# Schematic_Openbook.net
KiCad netlist of a schematic drawn in EAGLE
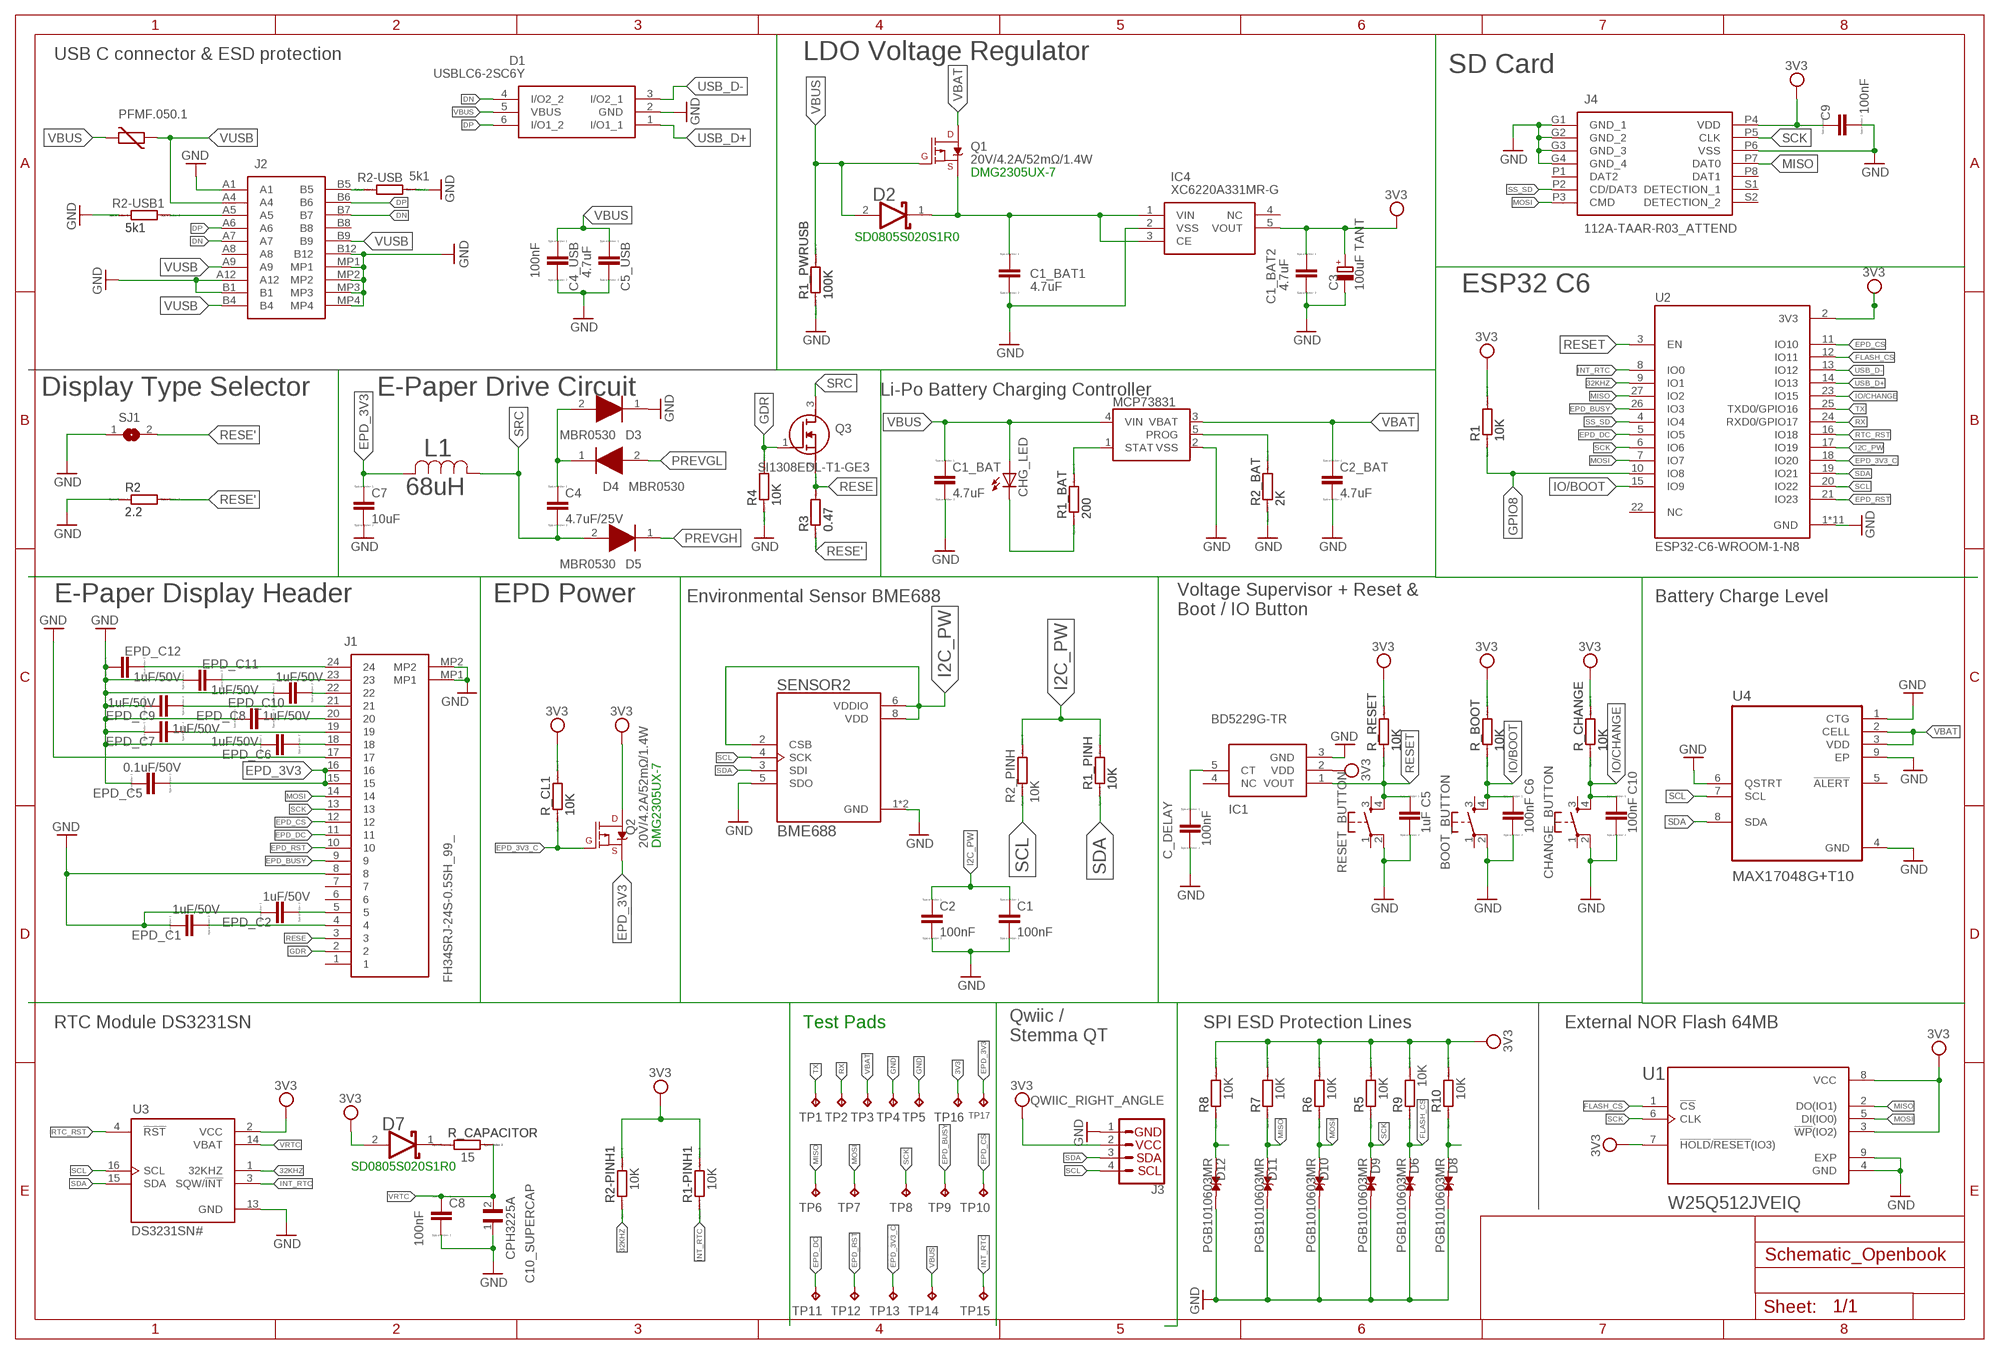
[diagram p0: schematic, sheet 1]

(export (version "E")
  (design (tool "Eeschema 10.0.6"))
  (components
    (comp (ref "BOOT_BUTTON")
      (value "BUTTON_CUSYOMV1")
      (footprint "eagle-import:MYBUTTON")
      (libsource (lib "eagle-import") (part "BUTTON_CUSYOMV1"))
    )
    (comp (ref "C1")
      (value "100nF")
      (footprint "eagle-import:ESP32_WROVER_EAGLE-LTSPICE_C0402")
      (libsource (lib "eagle-import") (part "ESP32_WROVER_EAGLE-LTSPICE_CC0402"))
    )
    (comp (ref "C1_BAT")
      (value "4.7uF")
      (footprint "eagle-import:ESP32_WROVER_EAGLE-LTSPICE_C0402")
      (libsource (lib "eagle-import") (part "ESP32_WROVER_EAGLE-LTSPICE_CC0402"))
    )
    (comp (ref "C1_BAT1")
      (value "4.7uF")
      (footprint "eagle-import:ESP32_WROVER_EAGLE-LTSPICE_C0402")
      (libsource (lib "eagle-import") (part "ESP32_WROVER_EAGLE-LTSPICE_CC0402"))
    )
    (comp (ref "C1_BAT2")
      (value "4.7uF")
      (footprint "eagle-import:ESP32_WROVER_EAGLE-LTSPICE_C0402")
      (libsource (lib "eagle-import") (part "ESP32_WROVER_EAGLE-LTSPICE_CC0402"))
    )
    (comp (ref "C2")
      (value "100nF")
      (footprint "eagle-import:ESP32_WROVER_EAGLE-LTSPICE_C0402")
      (libsource (lib "eagle-import") (part "ESP32_WROVER_EAGLE-LTSPICE_CC0402"))
    )
    (comp (ref "C2_BAT")
      (value "4.7uF")
      (footprint "eagle-import:ESP32_WROVER_EAGLE-LTSPICE_C0402")
      (libsource (lib "eagle-import") (part "ESP32_WROVER_EAGLE-LTSPICE_CC0402"))
    )
    (comp (ref "C3")
      (value "100uF TANT")
      (footprint "eagle-import:RCL_CT3528")
      (libsource (lib "eagle-import") (part "RCL_CPOL-EUCT3528"))
    )
    (comp (ref "C4")
      (value "4.7uF/25V")
      (footprint "eagle-import:ESP32_WROVER_EAGLE-LTSPICE_C0402")
      (libsource (lib "eagle-import") (part "ESP32_WROVER_EAGLE-LTSPICE_CC0402"))
    )
    (comp (ref "C4_USB")
      (value "100nF")
      (footprint "eagle-import:ESP32_WROVER_EAGLE-LTSPICE_C0402")
      (libsource (lib "eagle-import") (part "ESP32_WROVER_EAGLE-LTSPICE_CC0402"))
    )
    (comp (ref "C5")
      (value "1uF")
      (footprint "eagle-import:ESP32_WROVER_EAGLE-LTSPICE_C0402")
      (libsource (lib "eagle-import") (part "ESP32_WROVER_EAGLE-LTSPICE_CC0402"))
    )
    (comp (ref "C5_USB")
      (value "4.7uF")
      (footprint "eagle-import:ESP32_WROVER_EAGLE-LTSPICE_C0402")
      (libsource (lib "eagle-import") (part "ESP32_WROVER_EAGLE-LTSPICE_CC0402"))
    )
    (comp (ref "C6")
      (value "100nF")
      (footprint "eagle-import:ESP32_WROVER_EAGLE-LTSPICE_C0402")
      (libsource (lib "eagle-import") (part "ESP32_WROVER_EAGLE-LTSPICE_CC0402"))
    )
    (comp (ref "C7")
      (value "10uF")
      (footprint "eagle-import:ESP32_WROVER_EAGLE-LTSPICE_C0402")
      (libsource (lib "eagle-import") (part "ESP32_WROVER_EAGLE-LTSPICE_CC0402"))
    )
    (comp (ref "C8")
      (value "100nF")
      (footprint "eagle-import:ESP32_WROVER_EAGLE-LTSPICE_C0402")
      (libsource (lib "eagle-import") (part "ESP32_WROVER_EAGLE-LTSPICE_CC0402"))
    )
    (comp (ref "C9")
      (value "100nF")
      (footprint "eagle-import:ESP32_WROVER_EAGLE-LTSPICE_C0402")
      (libsource (lib "eagle-import") (part "ESP32_WROVER_EAGLE-LTSPICE_CC0402"))
    )
    (comp (ref "C10")
      (value "100nF")
      (footprint "eagle-import:ESP32_WROVER_EAGLE-LTSPICE_C0402")
      (libsource (lib "eagle-import") (part "ESP32_WROVER_EAGLE-LTSPICE_CC0402"))
    )
    (comp (ref "C10_SUPERCAP")
      (value "CPH3225A")
      (footprint "eagle-import:CAPCP3225X100N")
      (fields (field (name "MF") "Seiko Instruments"))
      (libsource (lib "eagle-import") (part "CPH3225A"))
    )
    (comp (ref "CHANGE_BUTTON")
      (value "BUTTON_CUSYOMV1")
      (footprint "eagle-import:MYBUTTON")
      (libsource (lib "eagle-import") (part "BUTTON_CUSYOMV1"))
    )
    (comp (ref "CHG_LED")
      (value "ADAFRUIT_LEDCHIP-LED0603")
      (footprint "eagle-import:ADAFRUIT_CHIP-LED0603")
      (libsource (lib "eagle-import") (part "ADAFRUIT_LEDCHIP-LED0603"))
    )
    (comp (ref "C_DELAY")
      (value "100nF")
      (footprint "eagle-import:ESP32_WROVER_EAGLE-LTSPICE_C0402")
      (libsource (lib "eagle-import") (part "ESP32_WROVER_EAGLE-LTSPICE_CC0402"))
    )
    (comp (ref "D1")
      (value "USBLC6-2SC6Y")
      (footprint "eagle-import:SOT95P280X145-6N")
      (fields (field (name "MF") "STMicroelectronics"))
      (libsource (lib "eagle-import") (part "USBLC6-2SC6Y"))
    )
    (comp (ref "D2")
      (value "SD0805S020S1R0")
      (footprint "eagle-import:ESP32_WROVER_AVX---SD0805S020S1R0_AVX_SD0805S020S1R0_0")
      (fields
        (field (name "DIGIKEY_PART_NUMBER") "478-7800-1-ND")
        (field (name "MF") "AVX")
        (field (name "MOUSER_PART_NUMBER") "581-SD0805S020S1R0")
      )
      (libsource (lib "eagle-import") (part "ESP32_WROVER_AVX---SD0805S020S1R0_AVX_SD0805S020S1R0_0_0AVX_SD0805S020S1R0_0_0"))
    )
    (comp (ref "D3")
      (value "MBR0530")
      (footprint "eagle-import:SOD3716X135N")
      (fields (field (name "MF") "ON Semiconductor"))
      (libsource (lib "eagle-import") (part "MBR0530"))
    )
    (comp (ref "D4")
      (value "MBR0530")
      (footprint "eagle-import:SOD3716X135N")
      (fields (field (name "MF") "ON Semiconductor"))
      (libsource (lib "eagle-import") (part "MBR0530"))
    )
    (comp (ref "D5")
      (value "MBR0530")
      (footprint "eagle-import:SOD3716X135N")
      (fields (field (name "MF") "ON Semiconductor"))
      (libsource (lib "eagle-import") (part "MBR0530"))
    )
    (comp (ref "D6")
      (value "PGB1010603MR")
      (footprint "eagle-import:DIOC1608X36N")
      (fields (field (name "MF") "Littelfuse Inc."))
      (libsource (lib "eagle-import") (part "PGB1010603MR"))
    )
    (comp (ref "D7")
      (value "SD0805S020S1R0")
      (footprint "eagle-import:ESP32_WROVER_AVX---SD0805S020S1R0_AVX_SD0805S020S1R0_0")
      (fields
        (field (name "DIGIKEY_PART_NUMBER") "478-7800-1-ND")
        (field (name "MF") "AVX")
        (field (name "MOUSER_PART_NUMBER") "581-SD0805S020S1R0")
      )
      (libsource (lib "eagle-import") (part "ESP32_WROVER_AVX---SD0805S020S1R0_AVX_SD0805S020S1R0_0_0AVX_SD0805S020S1R0_0_0"))
    )
    (comp (ref "D8")
      (value "PGB1010603MR")
      (footprint "eagle-import:DIOC1608X36N")
      (fields (field (name "MF") "Littelfuse Inc."))
      (libsource (lib "eagle-import") (part "PGB1010603MR"))
    )
    (comp (ref "D9")
      (value "PGB1010603MR")
      (footprint "eagle-import:DIOC1608X36N")
      (fields (field (name "MF") "Littelfuse Inc."))
      (libsource (lib "eagle-import") (part "PGB1010603MR"))
    )
    (comp (ref "D10")
      (value "PGB1010603MR")
      (footprint "eagle-import:DIOC1608X36N")
      (fields (field (name "MF") "Littelfuse Inc."))
      (libsource (lib "eagle-import") (part "PGB1010603MR"))
    )
    (comp (ref "D11")
      (value "PGB1010603MR")
      (footprint "eagle-import:DIOC1608X36N")
      (fields (field (name "MF") "Littelfuse Inc."))
      (libsource (lib "eagle-import") (part "PGB1010603MR"))
    )
    (comp (ref "D12")
      (value "PGB1010603MR")
      (footprint "eagle-import:DIOC1608X36N")
      (fields (field (name "MF") "Littelfuse Inc."))
      (libsource (lib "eagle-import") (part "PGB1010603MR"))
    )
    (comp (ref "EPD_C1")
      (value "1uF/50V")
      (footprint "eagle-import:ESP32_WROVER_EAGLE-LTSPICE_C0402")
      (libsource (lib "eagle-import") (part "ESP32_WROVER_EAGLE-LTSPICE_CC0402"))
    )
    (comp (ref "EPD_C2")
      (value "1uF/50V")
      (footprint "eagle-import:ESP32_WROVER_EAGLE-LTSPICE_C0402")
      (libsource (lib "eagle-import") (part "ESP32_WROVER_EAGLE-LTSPICE_CC0402"))
    )
    (comp (ref "EPD_C5")
      (value "0.1uF/50V")
      (footprint "eagle-import:ESP32_WROVER_EAGLE-LTSPICE_C0402")
      (libsource (lib "eagle-import") (part "ESP32_WROVER_EAGLE-LTSPICE_CC0402"))
    )
    (comp (ref "EPD_C6")
      (value "1uF/50V")
      (footprint "eagle-import:ESP32_WROVER_EAGLE-LTSPICE_C0402")
      (libsource (lib "eagle-import") (part "ESP32_WROVER_EAGLE-LTSPICE_CC0402"))
    )
    (comp (ref "EPD_C7")
      (value "1uF/50V")
      (footprint "eagle-import:ESP32_WROVER_EAGLE-LTSPICE_C0402")
      (libsource (lib "eagle-import") (part "ESP32_WROVER_EAGLE-LTSPICE_CC0402"))
    )
    (comp (ref "EPD_C8")
      (value "1uF/50V")
      (footprint "eagle-import:ESP32_WROVER_EAGLE-LTSPICE_C0402")
      (libsource (lib "eagle-import") (part "ESP32_WROVER_EAGLE-LTSPICE_CC0402"))
    )
    (comp (ref "EPD_C9")
      (value "1uF/50V")
      (footprint "eagle-import:ESP32_WROVER_EAGLE-LTSPICE_C0402")
      (libsource (lib "eagle-import") (part "ESP32_WROVER_EAGLE-LTSPICE_CC0402"))
    )
    (comp (ref "EPD_C10")
      (value "1uF/50V")
      (footprint "eagle-import:ESP32_WROVER_EAGLE-LTSPICE_C0402")
      (libsource (lib "eagle-import") (part "ESP32_WROVER_EAGLE-LTSPICE_CC0402"))
    )
    (comp (ref "EPD_C11")
      (value "1uF/50V")
      (footprint "eagle-import:ESP32_WROVER_EAGLE-LTSPICE_C0402")
      (libsource (lib "eagle-import") (part "ESP32_WROVER_EAGLE-LTSPICE_CC0402"))
    )
    (comp (ref "EPD_C12")
      (value "1uF/50V")
      (footprint "eagle-import:ESP32_WROVER_EAGLE-LTSPICE_C0402")
      (libsource (lib "eagle-import") (part "ESP32_WROVER_EAGLE-LTSPICE_CC0402"))
    )
    (comp (ref "IC1")
      (value "BD5229G-TR")
      (footprint "eagle-import:SOT95P280X125-5N")
      (fields (field (name "MOUSER_PART_NUMBER") "755-BD5229G-TR"))
      (libsource (lib "eagle-import") (part "BD5229G-TR"))
    )
    (comp (ref "IC4")
      (value "XC6220A331MR-G")
      (footprint "eagle-import:SOT95P280X120-5N")
      (fields (field (name "MOUSER_PART_NUMBER") "865-XC6220A331MR-G"))
      (libsource (lib "eagle-import") (part "XC6220A331MR-G"))
    )
    (comp (ref "J1")
      (value "FH34SRJ-24S-0.5SH_99_")
      (footprint "eagle-import:FH34SRJ24S05SH99")
      (fields
        (field (name "MANUFACTURER_PART_NUMBER") "FH34SRJ-24S-0.5SH(99)")
        (field (name "MOUSER_PART_NUMBER") "798-FH34SRJ24S05SH99")
      )
      (libsource (lib "eagle-import") (part "FH34SRJ-24S-0.5SH_99_"))
    )
    (comp (ref "J2")
      (value "SAMACSYS_PARTS_USB4110-GF-A")
      (footprint "eagle-import:SAMACSYS_PARTS_USB4110GFA")
      (fields
        (field (name "MANUFACTURER_PART_NUMBER") "USB4110-GF-A")
        (field (name "MOUSER_PART_NUMBER") "640-USB4110-GF-A")
      )
      (libsource (lib "eagle-import") (part "SAMACSYS_PARTS_USB4110-GF-A"))
    )
    (comp (ref "J3")
      (value "QWIIC_RIGHT_ANGLE")
      (footprint "eagle-import:JST04_1MM_RA")
      (libsource (lib "eagle-import") (part "QWIIC_CONNECTORJS-1MM"))
    )
    (comp (ref "J4")
      (value "112A-TAAR-R03_ATTEND")
      (footprint "eagle-import:112ATAARR03ATTEND")
      (fields (field (name "MANUFACTURER_PART_NUMBER") "112A-TAAR-R03 ATTEND"))
      (libsource (lib "eagle-import") (part "112A-TAAR-R03_ATTEND"))
    )
    (comp (ref "L1")
      (value "68uH")
      (footprint "eagle-import:IND_4828-WE-TPC_WRE")
      (fields
        (field (name "MANUFACTURER_PART_NUMBER") "744043680")
        (field (name "COPYRIGHT") "Copyright (C) 2024 Ultra Librarian. All rights reserved.")
      )
      (libsource (lib "eagle-import") (part "744043680IND_4828-WE-TPC_WRE"))
    )
    (comp (ref "MCP73831")
      (value "ESP32_WROVER_SPARKFUN-IC-POWER_MCP73831")
      (footprint "eagle-import:ESP32_WROVER_SPARKFUN-IC-POWER_SOT23-5")
      (libsource (lib "eagle-import") (part "ESP32_WROVER_SPARKFUN-IC-POWER_MCP73831"))
    )
    (comp (ref "PFMF.050.1")
      (value "ESP32C6_VARISTORCN1812")
      (footprint "eagle-import:ESP32C6_VARISTOR_CT_CN1812")
      (libsource (lib "eagle-import") (part "ESP32C6_VARISTORCN1812"))
    )
    (comp (ref "Q1")
      (value "20V/4.2A/52mΩ/1.4W")
      (footprint "eagle-import:ESP32_WROVER_SPARKFUN-DISCRETESEMI_SOT23-3")
      (libsource (lib "eagle-import") (part "ESP32_WROVER_SPARKFUN-DISCRETESEMI_MOSFET_PCH-DMG2305UX-7"))
    )
    (comp (ref "Q2")
      (value "20V/4.2A/52mΩ/1.4W")
      (footprint "eagle-import:ESP32_WROVER_SPARKFUN-DISCRETESEMI_SOT23-3")
      (libsource (lib "eagle-import") (part "ESP32_WROVER_SPARKFUN-DISCRETESEMI_MOSFET_PCH-DMG2305UX-7"))
    )
    (comp (ref "Q3")
      (value "SI1308EDL-T1-GE3")
      (footprint "eagle-import:SOT65P210X110-3N")
      (fields (field (name "MF") "Vishay Siliconix"))
      (libsource (lib "eagle-import") (part "SI1308EDL-T1-GE3"))
    )
    (comp (ref "R1")
      (value "10K")
      (footprint "eagle-import:ESP32_WROVER_EAGLE-LTSPICE_R0402")
      (libsource (lib "eagle-import") (part "ESP32_WROVER_EAGLE-LTSPICE_RR0402"))
    )
    (comp (ref "R1-PINH1")
      (value "10K")
      (footprint "eagle-import:ESP32_WROVER_EAGLE-LTSPICE_R0402")
      (libsource (lib "eagle-import") (part "ESP32_WROVER_EAGLE-LTSPICE_RR0402"))
    )
    (comp (ref "R1_BAT")
      (value "200")
      (footprint "eagle-import:ESP32_WROVER_EAGLE-LTSPICE_R0402")
      (libsource (lib "eagle-import") (part "ESP32_WROVER_EAGLE-LTSPICE_RR0402"))
    )
    (comp (ref "R1_PINH")
      (value "10K")
      (footprint "eagle-import:ESP32_WROVER_EAGLE-LTSPICE_R0402")
      (libsource (lib "eagle-import") (part "ESP32_WROVER_EAGLE-LTSPICE_RR0402"))
    )
    (comp (ref "R1_PWRUSB")
      (value "100K")
      (footprint "eagle-import:ESP32_WROVER_EAGLE-LTSPICE_R0402")
      (libsource (lib "eagle-import") (part "ESP32_WROVER_EAGLE-LTSPICE_RR0402"))
    )
    (comp (ref "R2")
      (value "2.2")
      (footprint "eagle-import:ESP32_WROVER_EAGLE-LTSPICE_R0402")
      (libsource (lib "eagle-import") (part "ESP32_WROVER_EAGLE-LTSPICE_RR0402"))
    )
    (comp (ref "R2-PINH1")
      (value "10K")
      (footprint "eagle-import:ESP32_WROVER_EAGLE-LTSPICE_R0402")
      (libsource (lib "eagle-import") (part "ESP32_WROVER_EAGLE-LTSPICE_RR0402"))
    )
    (comp (ref "R2-USB")
      (value "5k1")
      (footprint "eagle-import:ESP32_WROVER_EAGLE-LTSPICE_R0402")
      (libsource (lib "eagle-import") (part "ESP32_WROVER_EAGLE-LTSPICE_RR0402"))
    )
    (comp (ref "R2-USB1")
      (value "5k1")
      (footprint "eagle-import:ESP32_WROVER_EAGLE-LTSPICE_R0402")
      (libsource (lib "eagle-import") (part "ESP32_WROVER_EAGLE-LTSPICE_RR0402"))
    )
    (comp (ref "R2_BAT")
      (value "2K")
      (footprint "eagle-import:ESP32_WROVER_EAGLE-LTSPICE_R0402")
      (libsource (lib "eagle-import") (part "ESP32_WROVER_EAGLE-LTSPICE_RR0402"))
    )
    (comp (ref "R2_PINH")
      (value "10K")
      (footprint "eagle-import:ESP32_WROVER_EAGLE-LTSPICE_R0402")
      (libsource (lib "eagle-import") (part "ESP32_WROVER_EAGLE-LTSPICE_RR0402"))
    )
    (comp (ref "R3")
      (value "0.47")
      (footprint "eagle-import:ESP32_WROVER_EAGLE-LTSPICE_R0402")
      (libsource (lib "eagle-import") (part "ESP32_WROVER_EAGLE-LTSPICE_RR0402"))
    )
    (comp (ref "R4")
      (value "10K")
      (footprint "eagle-import:ESP32_WROVER_EAGLE-LTSPICE_R0402")
      (libsource (lib "eagle-import") (part "ESP32_WROVER_EAGLE-LTSPICE_RR0402"))
    )
    (comp (ref "R5")
      (value "10K")
      (footprint "eagle-import:ESP32_WROVER_EAGLE-LTSPICE_R0402")
      (libsource (lib "eagle-import") (part "ESP32_WROVER_EAGLE-LTSPICE_RR0402"))
    )
    (comp (ref "R6")
      (value "10K")
      (footprint "eagle-import:ESP32_WROVER_EAGLE-LTSPICE_R0402")
      (libsource (lib "eagle-import") (part "ESP32_WROVER_EAGLE-LTSPICE_RR0402"))
    )
    (comp (ref "R7")
      (value "10K")
      (footprint "eagle-import:ESP32_WROVER_EAGLE-LTSPICE_R0402")
      (libsource (lib "eagle-import") (part "ESP32_WROVER_EAGLE-LTSPICE_RR0402"))
    )
    (comp (ref "R8")
      (value "10K")
      (footprint "eagle-import:ESP32_WROVER_EAGLE-LTSPICE_R0402")
      (libsource (lib "eagle-import") (part "ESP32_WROVER_EAGLE-LTSPICE_RR0402"))
    )
    (comp (ref "R9")
      (value "10K")
      (footprint "eagle-import:ESP32_WROVER_EAGLE-LTSPICE_R0402")
      (libsource (lib "eagle-import") (part "ESP32_WROVER_EAGLE-LTSPICE_RR0402"))
    )
    (comp (ref "R10")
      (value "10K")
      (footprint "eagle-import:ESP32_WROVER_EAGLE-LTSPICE_R0402")
      (libsource (lib "eagle-import") (part "ESP32_WROVER_EAGLE-LTSPICE_RR0402"))
    )
    (comp (ref "RESET_BUTTON")
      (value "BUTTON_CUSYOMV1")
      (footprint "eagle-import:MYBUTTON")
      (libsource (lib "eagle-import") (part "BUTTON_CUSYOMV1"))
    )
    (comp (ref "R_BOOT")
      (value "10K")
      (footprint "eagle-import:ESP32_WROVER_EAGLE-LTSPICE_R0402")
      (libsource (lib "eagle-import") (part "ESP32_WROVER_EAGLE-LTSPICE_RR0402"))
    )
    (comp (ref "R_CAPACITOR")
      (value "15")
      (footprint "eagle-import:ESP32_WROVER_EAGLE-LTSPICE_R0402")
      (libsource (lib "eagle-import") (part "ESP32_WROVER_EAGLE-LTSPICE_RR0402"))
    )
    (comp (ref "R_CHANGE")
      (value "10K")
      (footprint "eagle-import:ESP32_WROVER_EAGLE-LTSPICE_R0402")
      (libsource (lib "eagle-import") (part "ESP32_WROVER_EAGLE-LTSPICE_RR0402"))
    )
    (comp (ref "R_CL1")
      (value "10K")
      (footprint "eagle-import:ESP32_WROVER_EAGLE-LTSPICE_R0402")
      (libsource (lib "eagle-import") (part "ESP32_WROVER_EAGLE-LTSPICE_RR0402"))
    )
    (comp (ref "R_RESET")
      (value "10K")
      (footprint "eagle-import:ESP32_WROVER_EAGLE-LTSPICE_R0402")
      (libsource (lib "eagle-import") (part "ESP32_WROVER_EAGLE-LTSPICE_RR0402"))
    )
    (comp (ref "SENSOR2")
      (value "BME688")
      (footprint "eagle-import:ESP32_WROVER_BME680_PSON80P300X300X100-8N")
      (fields (field (name "MF") "Bosch Sensortec") (field (name "MP") "BME680"))
      (libsource (lib "eagle-import") (part "ESP32_WROVER_BME680_BME680"))
    )
    (comp (ref "SJ1") (value "SJ") (footprint "eagle-import:SJ") (libsource (lib "eagle-import") (part "SJ")))
    (comp (ref "TP1")
      (value "TPTP20R")
      (footprint "eagle-import:TP20R")
      (libsource (lib "eagle-import") (part "TPTP20R"))
    )
    (comp (ref "TP2")
      (value "TPTP20R")
      (footprint "eagle-import:TP20R")
      (libsource (lib "eagle-import") (part "TPTP20R"))
    )
    (comp (ref "TP3")
      (value "TPTP20R")
      (footprint "eagle-import:TP20R")
      (libsource (lib "eagle-import") (part "TPTP20R"))
    )
    (comp (ref "TP4")
      (value "TPTP20R")
      (footprint "eagle-import:TP20R")
      (libsource (lib "eagle-import") (part "TPTP20R"))
    )
    (comp (ref "TP5")
      (value "TPTP20R")
      (footprint "eagle-import:TP20R")
      (libsource (lib "eagle-import") (part "TPTP20R"))
    )
    (comp (ref "TP6")
      (value "TPTP20R")
      (footprint "eagle-import:TP20R")
      (libsource (lib "eagle-import") (part "TPTP20R"))
    )
    (comp (ref "TP7")
      (value "TPTP20R")
      (footprint "eagle-import:TP20R")
      (libsource (lib "eagle-import") (part "TPTP20R"))
    )
    (comp (ref "TP8")
      (value "TPTP20R")
      (footprint "eagle-import:TP20R")
      (libsource (lib "eagle-import") (part "TPTP20R"))
    )
    (comp (ref "TP9")
      (value "TPTP20R")
      (footprint "eagle-import:TP20R")
      (libsource (lib "eagle-import") (part "TPTP20R"))
    )
    (comp (ref "TP10")
      (value "TPTP20R")
      (footprint "eagle-import:TP20R")
      (libsource (lib "eagle-import") (part "TPTP20R"))
    )
    (comp (ref "TP11")
      (value "TPTP20R")
      (footprint "eagle-import:TP20R")
      (libsource (lib "eagle-import") (part "TPTP20R"))
    )
    (comp (ref "TP12")
      (value "TPTP20R")
      (footprint "eagle-import:TP20R")
      (libsource (lib "eagle-import") (part "TPTP20R"))
    )
    (comp (ref "TP13")
      (value "TPTP20R")
      (footprint "eagle-import:TP20R")
      (libsource (lib "eagle-import") (part "TPTP20R"))
    )
    (comp (ref "TP14")
      (value "TPTP20R")
      (footprint "eagle-import:TP20R")
      (libsource (lib "eagle-import") (part "TPTP20R"))
    )
    (comp (ref "TP15")
      (value "TPTP20R")
      (footprint "eagle-import:TP20R")
      (libsource (lib "eagle-import") (part "TPTP20R"))
    )
    (comp (ref "TP16")
      (value "TPTP20R")
      (footprint "eagle-import:TP20R")
      (libsource (lib "eagle-import") (part "TPTP20R"))
    )
    (comp (ref "TP17")
      (value "TPTP20R")
      (footprint "eagle-import:TP20R")
      (libsource (lib "eagle-import") (part "TPTP20R"))
    )
    (comp (ref "U1")
      (value "W25Q512JVEIQ")
      (footprint "eagle-import:SON127P600X800X80-9N")
      (fields (field (name "MF") "Winbond Electronics"))
      (libsource (lib "eagle-import") (part "W25Q512JVEIQ"))
    )
    (comp (ref "U2")
      (value "ESP32-C6-WROOM-1-N8")
      (footprint "eagle-import:XCVR_ESP32-C6-WROOM-1-N8")
      (fields (field (name "MF") "Espressif Systems"))
      (libsource (lib "eagle-import") (part "ESP32-C6-WROOM-1-N8"))
    )
    (comp (ref "U3")
      (value "DS3231SN#")
      (footprint "eagle-import:SOIC127P1032X265-16N")
      (fields (field (name "MF") "Analog Devices"))
      (libsource (lib "eagle-import") (part "DS3231SN#"))
    )
    (comp (ref "U4")
      (value "MAX17048G+T10")
      (footprint "eagle-import:SON50P200X200X80-9N")
      (fields (field (name "MF") "Analog Devices"))
      (libsource (lib "eagle-import") (part "MAX17048G+T10"))
    )
  )
  (nets
    (net (code "1") (name "3V3") (class "Default")
      (node (ref "C1_BAT2") (pin "1") (pinfunction "1_1") (pintype "passive"))
      (node (ref "C3") (pin "+") (pinfunction "+_+") (pintype "passive"))
      (node (ref "C9") (pin "1") (pinfunction "1_1") (pintype "passive"))
      (node (ref "D7") (pin "2") (pinfunction "ANODE_2") (pintype "bidirectional"))
      (node (ref "IC1") (pin "2") (pinfunction "VDD_2") (pintype "bidirectional"))
      (node (ref "IC4") (pin "5") (pinfunction "VOUT_5") (pintype "bidirectional"))
      (node (ref "J3") (pin "2") (pinfunction "2_2") (pintype "power_in"))
      (node (ref "J4") (pin "P4") (pinfunction "VDD_P4") (pintype "bidirectional"))
      (node (ref "Q2") (pin "3") (pinfunction "D_3") (pintype "bidirectional"))
      (node (ref "R1") (pin "2") (pinfunction "2_2") (pintype "passive"))
      (node (ref "R1-PINH1") (pin "2") (pinfunction "2_2") (pintype "passive"))
      (node (ref "R10") (pin "2") (pinfunction "2_2") (pintype "passive"))
      (node (ref "R2-PINH1") (pin "2") (pinfunction "2_2") (pintype "passive"))
      (node (ref "R5") (pin "2") (pinfunction "2_2") (pintype "passive"))
      (node (ref "R6") (pin "2") (pinfunction "2_2") (pintype "passive"))
      (node (ref "R7") (pin "2") (pinfunction "2_2") (pintype "passive"))
      (node (ref "R8") (pin "2") (pinfunction "2_2") (pintype "passive"))
      (node (ref "R9") (pin "2") (pinfunction "2_2") (pintype "passive"))
      (node (ref "R_BOOT") (pin "2") (pinfunction "2_2") (pintype "passive"))
      (node (ref "R_CHANGE") (pin "2") (pinfunction "2_2") (pintype "passive"))
      (node (ref "R_CL1") (pin "2") (pinfunction "2_2") (pintype "passive"))
      (node (ref "R_RESET") (pin "2") (pinfunction "2_2") (pintype "passive"))
      (node (ref "TP16") (pin "TP") (pinfunction "TP_TP") (pintype "input"))
      (node (ref "U1") (pin "3") (pinfunction "~{WP}(IO2)_3") (pintype "bidirectional"))
      (node (ref "U1") (pin "7") (pinfunction "~{HOLD}/~{RESET}(IO3)_7") (pintype "bidirectional"))
      (node (ref "U1") (pin "8") (pinfunction "VCC_8") (pintype "power_in"))
      (node (ref "U2") (pin "2") (pinfunction "3V3_2") (pintype "power_in"))
      (node (ref "U3") (pin "2") (pinfunction "VCC_2") (pintype "power_in"))
    )
    (net (code "2") (name "32KHZ") (class "Default")
      (node (ref "R2-PINH1") (pin "1") (pinfunction "1_1") (pintype "passive"))
      (node (ref "U2") (pin "9") (pinfunction "IO1_9") (pintype "bidirectional"))
      (node (ref "U3") (pin "1") (pinfunction "32KHZ_1") (pintype "output"))
    )
    (net (code "3") (name "DN") (class "Default")
      (node (ref "D1") (pin "4") (pinfunction "I/O2_2_4") (pintype "bidirectional"))
      (node (ref "J2") (pin "A7") (pinfunction "A7_A7") (pintype "bidirectional"))
      (node (ref "J2") (pin "B7") (pinfunction "B7_B7") (pintype "bidirectional"))
    )
    (net (code "4") (name "DP") (class "Default")
      (node (ref "D1") (pin "6") (pinfunction "I/O1_2_6") (pintype "bidirectional"))
      (node (ref "J2") (pin "A6") (pinfunction "A6_A6") (pintype "bidirectional"))
      (node (ref "J2") (pin "B6") (pinfunction "B6_B6") (pintype "bidirectional"))
    )
    (net (code "5") (name "EPD_3V3") (class "Default")
      (node (ref "C7") (pin "1") (pinfunction "1_1") (pintype "passive"))
      (node (ref "EPD_C5") (pin "2") (pinfunction "2_2") (pintype "passive"))
      (node (ref "J1") (pin "15") (pinfunction "15_15") (pintype "bidirectional"))
      (node (ref "J1") (pin "16") (pinfunction "16_16") (pintype "bidirectional"))
      (node (ref "L1") (pin "2") (pinfunction "2_2") (pintype "passive"))
      (node (ref "Q2") (pin "2") (pinfunction "S_2") (pintype "bidirectional"))
      (node (ref "TP17") (pin "TP") (pinfunction "TP_TP") (pintype "input"))
    )
    (net (code "6") (name "EPD_3V3_C") (class "Default")
      (node (ref "Q2") (pin "1") (pinfunction "G_1") (pintype "bidirectional"))
      (node (ref "R_CL1") (pin "1") (pinfunction "1_1") (pintype "passive"))
      (node (ref "TP13") (pin "TP") (pinfunction "TP_TP") (pintype "input"))
      (node (ref "U2") (pin "18") (pinfunction "IO20_18") (pintype "bidirectional"))
    )
    (net (code "7") (name "EPD_BUSY") (class "Default")
      (node (ref "J1") (pin "9") (pinfunction "9_9") (pintype "bidirectional"))
      (node (ref "TP9") (pin "TP") (pinfunction "TP_TP") (pintype "input"))
      (node (ref "U2") (pin "26") (pinfunction "IO3_26") (pintype "bidirectional"))
    )
    (net (code "8") (name "EPD_CS") (class "Default")
      (node (ref "J1") (pin "12") (pinfunction "12_12") (pintype "bidirectional"))
      (node (ref "TP10") (pin "TP") (pinfunction "TP_TP") (pintype "input"))
      (node (ref "U2") (pin "11") (pinfunction "IO10_11") (pintype "bidirectional"))
    )
    (net (code "9") (name "EPD_DC") (class "Default")
      (node (ref "J1") (pin "11") (pinfunction "11_11") (pintype "bidirectional"))
      (node (ref "TP11") (pin "TP") (pinfunction "TP_TP") (pintype "input"))
      (node (ref "U2") (pin "5") (pinfunction "IO5_5") (pintype "bidirectional"))
    )
    (net (code "10") (name "EPD_RST") (class "Default")
      (node (ref "J1") (pin "10") (pinfunction "10_10") (pintype "bidirectional"))
      (node (ref "TP12") (pin "TP") (pinfunction "TP_TP") (pintype "input"))
      (node (ref "U2") (pin "21") (pinfunction "IO23_21") (pintype "bidirectional"))
    )
    (net (code "11") (name "FLASH_CS") (class "Default")
      (node (ref "D6") (pin "1") (pinfunction "1_1") (pintype "passive"))
      (node (ref "R9") (pin "1") (pinfunction "1_1") (pintype "passive"))
      (node (ref "U1") (pin "1") (pinfunction "~{CS}_1") (pintype "input"))
      (node (ref "U2") (pin "12") (pinfunction "IO11_12") (pintype "bidirectional"))
    )
    (net (code "12") (name "GDR") (class "Default")
      (node (ref "J1") (pin "2") (pinfunction "2_2") (pintype "bidirectional"))
      (node (ref "Q3") (pin "1") (pinfunction "G_1") (pintype "bidirectional"))
      (node (ref "R4") (pin "2") (pinfunction "2_2") (pintype "passive"))
    )
    (net (code "13") (name "GND") (class "Default")
      (node (ref "BOOT_BUTTON") (pin "2") (pinfunction "2_2") (pintype "passive"))
      (node (ref "C1") (pin "2") (pinfunction "2_2") (pintype "passive"))
      (node (ref "C10") (pin "2") (pinfunction "2_2") (pintype "passive"))
      (node (ref "C10_SUPERCAP") (pin "1") (pinfunction "1_1") (pintype "passive"))
      (node (ref "C1_BAT") (pin "2") (pinfunction "2_2") (pintype "passive"))
      (node (ref "C1_BAT1") (pin "2") (pinfunction "2_2") (pintype "passive"))
      (node (ref "C1_BAT2") (pin "2") (pinfunction "2_2") (pintype "passive"))
      (node (ref "C2") (pin "2") (pinfunction "2_2") (pintype "passive"))
      (node (ref "C2_BAT") (pin "2") (pinfunction "2_2") (pintype "passive"))
      (node (ref "C3") (pin "-") (pinfunction "-_-") (pintype "passive"))
      (node (ref "C4_USB") (pin "2") (pinfunction "2_2") (pintype "passive"))
      (node (ref "C5") (pin "2") (pinfunction "2_2") (pintype "passive"))
      (node (ref "C5_USB") (pin "2") (pinfunction "2_2") (pintype "passive"))
      (node (ref "C6") (pin "2") (pinfunction "2_2") (pintype "passive"))
      (node (ref "C7") (pin "2") (pinfunction "2_2") (pintype "passive"))
      (node (ref "C8") (pin "2") (pinfunction "2_2") (pintype "passive"))
      (node (ref "C9") (pin "2") (pinfunction "2_2") (pintype "passive"))
      (node (ref "CHANGE_BUTTON") (pin "2") (pinfunction "2_2") (pintype "passive"))
      (node (ref "C_DELAY") (pin "2") (pinfunction "2_2") (pintype "passive"))
      (node (ref "D1") (pin "2") (pinfunction "GND_2") (pintype "bidirectional"))
      (node (ref "D10") (pin "2") (pinfunction "2_2") (pintype "passive"))
      (node (ref "D11") (pin "2") (pinfunction "2_2") (pintype "passive"))
      (node (ref "D12") (pin "2") (pinfunction "2_2") (pintype "passive"))
      (node (ref "D3") (pin "1") (pinfunction "K_1") (pintype "bidirectional"))
      (node (ref "D6") (pin "2") (pinfunction "2_2") (pintype "passive"))
      (node (ref "D8") (pin "2") (pinfunction "2_2") (pintype "passive"))
      (node (ref "D9") (pin "2") (pinfunction "2_2") (pintype "passive"))
      (node (ref "EPD_C1") (pin "1") (pinfunction "1_1") (pintype "passive"))
      (node (ref "EPD_C10") (pin "1") (pinfunction "1_1") (pintype "passive"))
      (node (ref "EPD_C11") (pin "1") (pinfunction "1_1") (pintype "passive"))
      (node (ref "EPD_C12") (pin "1") (pinfunction "1_1") (pintype "passive"))
      (node (ref "EPD_C2") (pin "1") (pinfunction "1_1") (pintype "passive"))
      (node (ref "EPD_C5") (pin "1") (pinfunction "1_1") (pintype "passive"))
      (node (ref "EPD_C6") (pin "1") (pinfunction "1_1") (pintype "passive"))
      (node (ref "EPD_C7") (pin "1") (pinfunction "1_1") (pintype "passive"))
      (node (ref "EPD_C8") (pin "1") (pinfunction "1_1") (pintype "passive"))
      (node (ref "EPD_C9") (pin "1") (pinfunction "1_1") (pintype "passive"))
      (node (ref "IC1") (pin "3") (pinfunction "GND_3") (pintype "bidirectional"))
      (node (ref "IC4") (pin "2") (pinfunction "VSS_2") (pintype "bidirectional"))
      (node (ref "J1") (pin "17") (pinfunction "17_17") (pintype "bidirectional"))
      (node (ref "J1") (pin "8") (pinfunction "8_8") (pintype "bidirectional"))
      (node (ref "J1") (pin "MP1") (pinfunction "MP1_MP1") (pintype "bidirectional"))
      (node (ref "J1") (pin "MP2") (pinfunction "MP2_MP2") (pintype "bidirectional"))
      (node (ref "J2") (pin "A1") (pinfunction "A1_A1") (pintype "bidirectional"))
      (node (ref "J2") (pin "A12") (pinfunction "A12_A12") (pintype "bidirectional"))
      (node (ref "J2") (pin "B1") (pinfunction "B1_B1") (pintype "bidirectional"))
      (node (ref "J2") (pin "B12") (pinfunction "B12_B12") (pintype "bidirectional"))
      (node (ref "J2") (pin "MP1") (pinfunction "MP1_MP1") (pintype "bidirectional"))
      (node (ref "J2") (pin "MP2") (pinfunction "MP2_MP2") (pintype "bidirectional"))
      (node (ref "J2") (pin "MP3") (pinfunction "MP3_MP3") (pintype "bidirectional"))
      (node (ref "J2") (pin "MP4") (pinfunction "MP4_MP4") (pintype "bidirectional"))
      (node (ref "J3") (pin "1") (pinfunction "1_1") (pintype "power_in"))
      (node (ref "J4") (pin "G1") (pinfunction "GND_1_G1") (pintype "bidirectional"))
      (node (ref "J4") (pin "G2") (pinfunction "GND_2_G2") (pintype "bidirectional"))
      (node (ref "J4") (pin "G3") (pinfunction "GND_3_G3") (pintype "bidirectional"))
      (node (ref "J4") (pin "G4") (pinfunction "GND_4_G4") (pintype "bidirectional"))
      (node (ref "J4") (pin "P6") (pinfunction "VSS_P6") (pintype "bidirectional"))
      (node (ref "MCP73831") (pin "2") (pinfunction "VSS_2") (pintype "power_in"))
      (node (ref "R1_PWRUSB") (pin "1") (pinfunction "1_1") (pintype "passive"))
      (node (ref "R2") (pin "1") (pinfunction "1_1") (pintype "passive"))
      (node (ref "R2-USB") (pin "2") (pinfunction "2_2") (pintype "passive"))
      (node (ref "R2-USB1") (pin "1") (pinfunction "1_1") (pintype "passive"))
      (node (ref "R2_BAT") (pin "1") (pinfunction "1_1") (pintype "passive"))
      (node (ref "R4") (pin "1") (pinfunction "1_1") (pintype "passive"))
      (node (ref "RESET_BUTTON") (pin "2") (pinfunction "2_2") (pintype "passive"))
      (node (ref "SENSOR2") (pin "1") (pinfunction "GND_1") (pintype "power_in"))
      (node (ref "SENSOR2") (pin "5") (pinfunction "SDO_5") (pintype "bidirectional"))
      (node (ref "SENSOR2") (pin "7") (pinfunction "GND_7") (pintype "power_in"))
      (node (ref "SJ1") (pin "1") (pinfunction "1_1") (pintype "passive"))
      (node (ref "TP4") (pin "TP") (pinfunction "TP_TP") (pintype "input"))
      (node (ref "TP5") (pin "TP") (pinfunction "TP_TP") (pintype "input"))
      (node (ref "U1") (pin "4") (pinfunction "GND_4") (pintype "power_in"))
      (node (ref "U1") (pin "9") (pinfunction "EXP_9") (pintype "passive"))
      (node (ref "U2") (pin "1") (pinfunction "GND_1") (pintype "power_in"))
      (node (ref "U2") (pin "28") (pinfunction "GND_28") (pintype "power_in"))
      (node (ref "U2") (pin "29_1") (pinfunction "GND_29_1") (pintype "power_in"))
      (node (ref "U2") (pin "29_2") (pinfunction "GND_29_2") (pintype "power_in"))
      (node (ref "U2") (pin "29_3") (pinfunction "GND_29_3") (pintype "power_in"))
      (node (ref "U2") (pin "29_4") (pinfunction "GND_29_4") (pintype "power_in"))
      (node (ref "U2") (pin "29_5") (pinfunction "GND_29_5") (pintype "power_in"))
      (node (ref "U2") (pin "29_6") (pinfunction "GND_29_6") (pintype "power_in"))
      (node (ref "U2") (pin "29_7") (pinfunction "GND_29_7") (pintype "power_in"))
      (node (ref "U2") (pin "29_8") (pinfunction "GND_29_8") (pintype "power_in"))
      (node (ref "U2") (pin "29_9") (pinfunction "GND_29_9") (pintype "power_in"))
      (node (ref "U3") (pin "13") (pinfunction "GND_13") (pintype "power_in"))
      (node (ref "U4") (pin "1") (pinfunction "CTG_1") (pintype "power_in"))
      (node (ref "U4") (pin "4") (pinfunction "GND_4") (pintype "power_in"))
      (node (ref "U4") (pin "6") (pinfunction "QSTRT_6") (pintype "input"))
      (node (ref "U4") (pin "9") (pinfunction "EP_9") (pintype "power_in"))
    )
    (net (code "14") (name "GPIO8") (class "Default")
      (node (ref "R1") (pin "1") (pinfunction "1_1") (pintype "passive"))
      (node (ref "U2") (pin "10") (pinfunction "IO8_10") (pintype "bidirectional"))
    )
    (net (code "15") (name "I2C_PW") (class "Default")
      (node (ref "C1") (pin "1") (pinfunction "1_1") (pintype "passive"))
      (node (ref "C2") (pin "1") (pinfunction "1_1") (pintype "passive"))
      (node (ref "R1_PINH") (pin "2") (pinfunction "2_2") (pintype "passive"))
      (node (ref "R2_PINH") (pin "2") (pinfunction "2_2") (pintype "passive"))
      (node (ref "SENSOR2") (pin "2") (pinfunction "CSB_2") (pintype "input"))
      (node (ref "SENSOR2") (pin "6") (pinfunction "VDDIO_6") (pintype "power_in"))
      (node (ref "SENSOR2") (pin "8") (pinfunction "VDD_8") (pintype "power_in"))
      (node (ref "U2") (pin "17") (pinfunction "IO19_17") (pintype "bidirectional"))
    )
    (net (code "16") (name "INT_RTC") (class "Default")
      (node (ref "R1-PINH1") (pin "1") (pinfunction "1_1") (pintype "passive"))
      (node (ref "TP15") (pin "TP") (pinfunction "TP_TP") (pintype "input"))
      (node (ref "U2") (pin "8") (pinfunction "IO0_8") (pintype "bidirectional"))
      (node (ref "U3") (pin "3") (pinfunction "SQW/~{INT}_3") (pintype "output"))
    )
    (net (code "17") (name "IO{slash}BOOT") (class "Default")
      (node (ref "BOOT_BUTTON") (pin "4") (pinfunction "4_4") (pintype "passive"))
      (node (ref "C6") (pin "1") (pinfunction "1_1") (pintype "passive"))
      (node (ref "R_BOOT") (pin "1") (pinfunction "1_1") (pintype "passive"))
      (node (ref "U2") (pin "15") (pinfunction "IO9_15") (pintype "bidirectional"))
    )
    (net (code "18") (name "IO{slash}CHANGE") (class "Default")
      (node (ref "C10") (pin "1") (pinfunction "1_1") (pintype "passive"))
      (node (ref "CHANGE_BUTTON") (pin "4") (pinfunction "4_4") (pintype "passive"))
      (node (ref "R_CHANGE") (pin "1") (pinfunction "1_1") (pintype "passive"))
      (node (ref "U2") (pin "23") (pinfunction "IO15_23") (pintype "bidirectional"))
    )
    (net (code "19") (name "MISO") (class "Default")
      (node (ref "D11") (pin "1") (pinfunction "1_1") (pintype "passive"))
      (node (ref "J4") (pin "P7") (pinfunction "DAT0_P7") (pintype "bidirectional"))
      (node (ref "R7") (pin "1") (pinfunction "1_1") (pintype "passive"))
      (node (ref "TP6") (pin "TP") (pinfunction "TP_TP") (pintype "input"))
      (node (ref "U1") (pin "2") (pinfunction "DO(IO1)_2") (pintype "bidirectional"))
      (node (ref "U2") (pin "27") (pinfunction "IO2_27") (pintype "bidirectional"))
    )
    (net (code "20") (name "MOSI") (class "Default")
      (node (ref "D10") (pin "1") (pinfunction "1_1") (pintype "passive"))
      (node (ref "J1") (pin "14") (pinfunction "14_14") (pintype "bidirectional"))
      (node (ref "J4") (pin "P3") (pinfunction "CMD_P3") (pintype "bidirectional"))
      (node (ref "R6") (pin "1") (pinfunction "1_1") (pintype "passive"))
      (node (ref "TP7") (pin "TP") (pinfunction "TP_TP") (pintype "input"))
      (node (ref "U1") (pin "5") (pinfunction "DI(IO0)_5") (pintype "bidirectional"))
      (node (ref "U2") (pin "7") (pinfunction "IO7_7") (pintype "bidirectional"))
    )
    (net (code "21") (name "Net-(CHG_LED-PadC)") (class "Default")
      (node (ref "CHG_LED") (pin "C") (pinfunction "C_C") (pintype "passive"))
      (node (ref "R1_BAT") (pin "1") (pinfunction "1_1") (pintype "passive"))
    )
    (net (code "22") (name "Net-(D2-CATHODE)") (class "Default")
      (node (ref "C1_BAT1") (pin "1") (pinfunction "1_1") (pintype "passive"))
      (node (ref "D2") (pin "1") (pinfunction "CATHODE_1") (pintype "bidirectional"))
      (node (ref "IC4") (pin "1") (pinfunction "VIN_1") (pintype "bidirectional"))
      (node (ref "IC4") (pin "3") (pinfunction "CE_3") (pintype "bidirectional"))
      (node (ref "Q1") (pin "2") (pinfunction "S_2") (pintype "bidirectional"))
    )
    (net (code "23") (name "Net-(D3-A)") (class "Default")
      (node (ref "C4") (pin "1") (pinfunction "1_1") (pintype "passive"))
      (node (ref "D3") (pin "2") (pinfunction "A_2") (pintype "bidirectional"))
      (node (ref "D4") (pin "1") (pinfunction "K_1") (pintype "bidirectional"))
    )
    (net (code "24") (name "Net-(D7-CATHODE)") (class "Default")
      (node (ref "D7") (pin "1") (pinfunction "CATHODE_1") (pintype "bidirectional"))
      (node (ref "R_CAPACITOR") (pin "1") (pinfunction "1_1") (pintype "passive"))
    )
    (net (code "25") (name "Net-(D8-Pad1)") (class "Default")
      (node (ref "D8") (pin "1") (pinfunction "1_1") (pintype "passive"))
      (node (ref "R10") (pin "1") (pinfunction "1_1") (pintype "passive"))
    )
    (net (code "26") (name "Net-(D12-Pad1)") (class "Default")
      (node (ref "D12") (pin "1") (pinfunction "1_1") (pintype "passive"))
      (node (ref "R8") (pin "1") (pinfunction "1_1") (pintype "passive"))
    )
    (net (code "27") (name "Net-(EPD_C1-Pad2)") (class "Default")
      (node (ref "EPD_C1") (pin "2") (pinfunction "2_2") (pintype "passive"))
      (node (ref "J1") (pin "4") (pinfunction "4_4") (pintype "bidirectional"))
    )
    (net (code "28") (name "Net-(EPD_C2-Pad2)") (class "Default")
      (node (ref "EPD_C2") (pin "2") (pinfunction "2_2") (pintype "passive"))
      (node (ref "J1") (pin "5") (pinfunction "5_5") (pintype "bidirectional"))
    )
    (net (code "29") (name "Net-(EPD_C6-Pad2)") (class "Default")
      (node (ref "EPD_C6") (pin "2") (pinfunction "2_2") (pintype "passive"))
      (node (ref "J1") (pin "18") (pinfunction "18_18") (pintype "bidirectional"))
    )
    (net (code "30") (name "Net-(EPD_C7-Pad2)") (class "Default")
      (node (ref "EPD_C7") (pin "2") (pinfunction "2_2") (pintype "passive"))
      (node (ref "J1") (pin "19") (pinfunction "19_19") (pintype "bidirectional"))
    )
    (net (code "31") (name "Net-(EPD_C8-Pad2)") (class "Default")
      (node (ref "EPD_C8") (pin "2") (pinfunction "2_2") (pintype "passive"))
      (node (ref "J1") (pin "20") (pinfunction "20_20") (pintype "bidirectional"))
    )
    (net (code "32") (name "Net-(EPD_C9-Pad2)") (class "Default")
      (node (ref "EPD_C9") (pin "2") (pinfunction "2_2") (pintype "passive"))
      (node (ref "J1") (pin "21") (pinfunction "21_21") (pintype "bidirectional"))
    )
    (net (code "33") (name "Net-(EPD_C10-Pad2)") (class "Default")
      (node (ref "EPD_C10") (pin "2") (pinfunction "2_2") (pintype "passive"))
      (node (ref "J1") (pin "22") (pinfunction "22_22") (pintype "bidirectional"))
    )
    (net (code "34") (name "Net-(EPD_C11-Pad2)") (class "Default")
      (node (ref "EPD_C11") (pin "2") (pinfunction "2_2") (pintype "passive"))
      (node (ref "J1") (pin "23") (pinfunction "23_23") (pintype "bidirectional"))
    )
    (net (code "35") (name "Net-(EPD_C12-Pad2)") (class "Default")
      (node (ref "EPD_C12") (pin "2") (pinfunction "2_2") (pintype "passive"))
      (node (ref "J1") (pin "24") (pinfunction "24_24") (pintype "bidirectional"))
    )
    (net (code "36") (name "Net-(IC1-CT)") (class "Default")
      (node (ref "C_DELAY") (pin "1") (pinfunction "1_1") (pintype "passive"))
      (node (ref "IC1") (pin "5") (pinfunction "CT_5") (pintype "bidirectional"))
    )
    (net (code "37") (name "Net-(J2-PadA5)") (class "Default")
      (node (ref "J2") (pin "A5") (pinfunction "A5_A5") (pintype "bidirectional"))
      (node (ref "R2-USB1") (pin "2") (pinfunction "2_2") (pintype "passive"))
    )
    (net (code "38") (name "Net-(J2-PadB5)") (class "Default")
      (node (ref "J2") (pin "B5") (pinfunction "B5_B5") (pintype "bidirectional"))
      (node (ref "R2-USB") (pin "1") (pinfunction "1_1") (pintype "passive"))
    )
    (net (code "39") (name "Net-(MCP73831-PROG)") (class "Default")
      (node (ref "MCP73831") (pin "5") (pinfunction "PROG_5") (pintype "input"))
      (node (ref "R2_BAT") (pin "2") (pinfunction "2_2") (pintype "passive"))
    )
    (net (code "40") (name "Net-(MCP73831-STAT)") (class "Default")
      (node (ref "MCP73831") (pin "1") (pinfunction "STAT_1") (pintype "output"))
      (node (ref "R1_BAT") (pin "2") (pinfunction "2_2") (pintype "passive"))
    )
    (net (code "41") (name "PREVGH") (class "Default")
      (node (ref "D5") (pin "1") (pinfunction "K_1") (pintype "bidirectional"))
    )
    (net (code "42") (name "PREVGL") (class "Default")
      (node (ref "D4") (pin "2") (pinfunction "A_2") (pintype "bidirectional"))
    )
    (net (code "43") (name "RESE") (class "Default")
      (node (ref "J1") (pin "3") (pinfunction "3_3") (pintype "bidirectional"))
      (node (ref "Q3") (pin "2") (pinfunction "S_2") (pintype "bidirectional"))
      (node (ref "R3") (pin "2") (pinfunction "2_2") (pintype "passive"))
    )
    (net (code "44") (name "RESE'") (class "Default")
      (node (ref "R2") (pin "2") (pinfunction "2_2") (pintype "passive"))
      (node (ref "R3") (pin "1") (pinfunction "1_1") (pintype "passive"))
      (node (ref "SJ1") (pin "2") (pinfunction "2_2") (pintype "passive"))
    )
    (net (code "45") (name "RESET") (class "Default")
      (node (ref "C5") (pin "1") (pinfunction "1_1") (pintype "passive"))
      (node (ref "IC1") (pin "1") (pinfunction "VOUT_1") (pintype "bidirectional"))
      (node (ref "RESET_BUTTON") (pin "4") (pinfunction "4_4") (pintype "passive"))
      (node (ref "R_RESET") (pin "1") (pinfunction "1_1") (pintype "passive"))
      (node (ref "U2") (pin "3") (pinfunction "EN_3") (pintype "input"))
    )
    (net (code "46") (name "RTC_RST") (class "Default")
      (node (ref "U2") (pin "16") (pinfunction "IO18_16") (pintype "bidirectional"))
      (node (ref "U3") (pin "4") (pinfunction "~{RST}_4") (pintype "input"))
    )
    (net (code "47") (name "RX") (class "Default")
      (node (ref "TP2") (pin "TP") (pinfunction "TP_TP") (pintype "input"))
      (node (ref "U2") (pin "24") (pinfunction "RXD0/GPIO17_24") (pintype "bidirectional"))
    )
    (net (code "48") (name "SCK") (class "Default")
      (node (ref "D9") (pin "1") (pinfunction "1_1") (pintype "passive"))
      (node (ref "J1") (pin "13") (pinfunction "13_13") (pintype "bidirectional"))
      (node (ref "J4") (pin "P5") (pinfunction "CLK_P5") (pintype "bidirectional"))
      (node (ref "R5") (pin "1") (pinfunction "1_1") (pintype "passive"))
      (node (ref "TP8") (pin "TP") (pinfunction "TP_TP") (pintype "input"))
      (node (ref "U1") (pin "6") (pinfunction "CLK_6") (pintype "input"))
      (node (ref "U2") (pin "6") (pinfunction "IO6_6") (pintype "bidirectional"))
    )
    (net (code "49") (name "SCL") (class "Default")
      (node (ref "J3") (pin "4") (pinfunction "4_4") (pintype "passive"))
      (node (ref "R2_PINH") (pin "1") (pinfunction "1_1") (pintype "passive"))
      (node (ref "SENSOR2") (pin "4") (pinfunction "SCK_4") (pintype "input"))
      (node (ref "U2") (pin "20") (pinfunction "IO22_20") (pintype "bidirectional"))
      (node (ref "U3") (pin "16") (pinfunction "SCL_16") (pintype "input"))
      (node (ref "U4") (pin "7") (pinfunction "SCL_7") (pintype "input"))
    )
    (net (code "50") (name "SDA") (class "Default")
      (node (ref "J3") (pin "3") (pinfunction "3_3") (pintype "passive"))
      (node (ref "R1_PINH") (pin "1") (pinfunction "1_1") (pintype "passive"))
      (node (ref "SENSOR2") (pin "3") (pinfunction "SDI_3") (pintype "bidirectional"))
      (node (ref "U2") (pin "19") (pinfunction "IO21_19") (pintype "bidirectional"))
      (node (ref "U3") (pin "15") (pinfunction "SDA_15") (pintype "bidirectional"))
      (node (ref "U4") (pin "8") (pinfunction "SDA_8") (pintype "bidirectional"))
    )
    (net (code "51") (name "SRC") (class "Default")
      (node (ref "C4") (pin "2") (pinfunction "2_2") (pintype "passive"))
      (node (ref "D5") (pin "2") (pinfunction "A_2") (pintype "bidirectional"))
      (node (ref "L1") (pin "1") (pinfunction "1_1") (pintype "passive"))
      (node (ref "Q3") (pin "3") (pinfunction "D_3") (pintype "bidirectional"))
    )
    (net (code "52") (name "SS_SD") (class "Default")
      (node (ref "J4") (pin "P2") (pinfunction "CD/DAT3_P2") (pintype "bidirectional"))
      (node (ref "U2") (pin "4") (pinfunction "IO4_4") (pintype "bidirectional"))
    )
    (net (code "53") (name "TX") (class "Default")
      (node (ref "TP1") (pin "TP") (pinfunction "TP_TP") (pintype "input"))
      (node (ref "U2") (pin "25") (pinfunction "TXD0/GPIO16_25") (pintype "bidirectional"))
    )
    (net (code "54") (name "USB_D+") (class "Default")
      (node (ref "D1") (pin "1") (pinfunction "I/O1_1_1") (pintype "bidirectional"))
      (node (ref "U2") (pin "14") (pinfunction "IO13_14") (pintype "bidirectional"))
    )
    (net (code "55") (name "USB_D-") (class "Default")
      (node (ref "D1") (pin "3") (pinfunction "I/O2_1_3") (pintype "bidirectional"))
      (node (ref "U2") (pin "13") (pinfunction "IO12_13") (pintype "bidirectional"))
    )
    (net (code "56") (name "VBAT") (class "Default")
      (node (ref "C2_BAT") (pin "1") (pinfunction "1_1") (pintype "passive"))
      (node (ref "MCP73831") (pin "3") (pinfunction "VBAT_3") (pintype "power_in"))
      (node (ref "Q1") (pin "3") (pinfunction "D_3") (pintype "bidirectional"))
      (node (ref "TP3") (pin "TP") (pinfunction "TP_TP") (pintype "input"))
      (node (ref "U4") (pin "2") (pinfunction "CELL_2") (pintype "power_in"))
      (node (ref "U4") (pin "3") (pinfunction "VDD_3") (pintype "power_in"))
    )
    (net (code "57") (name "VBUS") (class "Default")
      (node (ref "C1_BAT") (pin "1") (pinfunction "1_1") (pintype "passive"))
      (node (ref "C4_USB") (pin "1") (pinfunction "1_1") (pintype "passive"))
      (node (ref "C5_USB") (pin "1") (pinfunction "1_1") (pintype "passive"))
      (node (ref "CHG_LED") (pin "A") (pinfunction "A_A") (pintype "passive"))
      (node (ref "D1") (pin "5") (pinfunction "VBUS_5") (pintype "bidirectional"))
      (node (ref "D2") (pin "2") (pinfunction "ANODE_2") (pintype "bidirectional"))
      (node (ref "MCP73831") (pin "4") (pinfunction "VIN_4") (pintype "power_in"))
      (node (ref "PFMF.050.1") (pin "2") (pinfunction "2_2") (pintype "passive"))
      (node (ref "Q1") (pin "1") (pinfunction "G_1") (pintype "bidirectional"))
      (node (ref "R1_PWRUSB") (pin "2") (pinfunction "2_2") (pintype "passive"))
      (node (ref "TP14") (pin "TP") (pinfunction "TP_TP") (pintype "input"))
    )
    (net (code "58") (name "VRTC") (class "Default")
      (node (ref "C10_SUPERCAP") (pin "2") (pinfunction "2_2") (pintype "passive"))
      (node (ref "C8") (pin "1") (pinfunction "1_1") (pintype "passive"))
      (node (ref "R_CAPACITOR") (pin "2") (pinfunction "2_2") (pintype "passive"))
      (node (ref "U3") (pin "14") (pinfunction "VBAT_14") (pintype "power_in"))
    )
    (net (code "59") (name "VUSB") (class "Default")
      (node (ref "J2") (pin "A4") (pinfunction "A4_A4") (pintype "bidirectional"))
      (node (ref "J2") (pin "A9") (pinfunction "A9_A9") (pintype "bidirectional"))
      (node (ref "J2") (pin "B4") (pinfunction "B4_B4") (pintype "bidirectional"))
      (node (ref "J2") (pin "B9") (pinfunction "B9_B9") (pintype "bidirectional"))
      (node (ref "PFMF.050.1") (pin "1") (pinfunction "1_1") (pintype "passive"))
    )
    (net (code "60") (name "unconnected-(BOOT_BUTTON-Pad1)") (class "Default")
      (node (ref "BOOT_BUTTON") (pin "1") (pinfunction "1_1") (pintype "passive"))
    )
    (net (code "61") (name "unconnected-(BOOT_BUTTON-Pad3)") (class "Default")
      (node (ref "BOOT_BUTTON") (pin "3") (pinfunction "3_3") (pintype "passive"))
    )
    (net (code "62") (name "unconnected-(CHANGE_BUTTON-Pad1)") (class "Default")
      (node (ref "CHANGE_BUTTON") (pin "1") (pinfunction "1_1") (pintype "passive"))
    )
    (net (code "63") (name "unconnected-(CHANGE_BUTTON-Pad3)") (class "Default")
      (node (ref "CHANGE_BUTTON") (pin "3") (pinfunction "3_3") (pintype "passive"))
    )
    (net (code "64") (name "unconnected-(IC1-NC-Pad4)") (class "Default")
      (node (ref "IC1") (pin "4") (pinfunction "NC_4") (pintype "no_connect"))
    )
    (net (code "65") (name "unconnected-(IC4-NC-Pad4)") (class "Default")
      (node (ref "IC4") (pin "4") (pinfunction "NC_4") (pintype "no_connect"))
    )
    (net (code "66") (name "unconnected-(J1-Pad1)") (class "Default")
      (node (ref "J1") (pin "1") (pinfunction "1_1") (pintype "bidirectional"))
    )
    (net (code "67") (name "unconnected-(J1-Pad6)") (class "Default")
      (node (ref "J1") (pin "6") (pinfunction "6_6") (pintype "bidirectional"))
    )
    (net (code "68") (name "unconnected-(J1-Pad7)") (class "Default")
      (node (ref "J1") (pin "7") (pinfunction "7_7") (pintype "bidirectional"))
    )
    (net (code "69") (name "unconnected-(J2-PadA8)") (class "Default")
      (node (ref "J2") (pin "A8") (pinfunction "A8_A8") (pintype "bidirectional"))
    )
    (net (code "70") (name "unconnected-(J2-PadB8)") (class "Default")
      (node (ref "J2") (pin "B8") (pinfunction "B8_B8") (pintype "bidirectional"))
    )
    (net (code "71") (name "unconnected-(J4-DAT1-PadP8)") (class "Default")
      (node (ref "J4") (pin "P8") (pinfunction "DAT1_P8") (pintype "bidirectional"))
    )
    (net (code "72") (name "unconnected-(J4-DAT2-PadP1)") (class "Default")
      (node (ref "J4") (pin "P1") (pinfunction "DAT2_P1") (pintype "bidirectional"))
    )
    (net (code "73") (name "unconnected-(J4-DETECTION_1-PadS1)") (class "Default")
      (node (ref "J4") (pin "S1") (pinfunction "DETECTION_1_S1") (pintype "bidirectional"))
    )
    (net (code "74") (name "unconnected-(J4-DETECTION_2-PadS2)") (class "Default")
      (node (ref "J4") (pin "S2") (pinfunction "DETECTION_2_S2") (pintype "bidirectional"))
    )
    (net (code "75") (name "unconnected-(RESET_BUTTON-Pad1)") (class "Default")
      (node (ref "RESET_BUTTON") (pin "1") (pinfunction "1_1") (pintype "passive"))
    )
    (net (code "76") (name "unconnected-(RESET_BUTTON-Pad3)") (class "Default")
      (node (ref "RESET_BUTTON") (pin "3") (pinfunction "3_3") (pintype "passive"))
    )
    (net (code "77") (name "unconnected-(U2-NC-Pad22)") (class "Default")
      (node (ref "U2") (pin "22") (pinfunction "NC_22") (pintype "no_connect"))
    )
    (net (code "78") (name "unconnected-(U4-~{ALERT}-Pad5)") (class "Default")
      (node (ref "U4") (pin "5") (pinfunction "~{ALERT}_5") (pintype "output"))
    )
  )
)
